# vrs6907.net
KiCad netlist of a schematic drawn in EAGLE
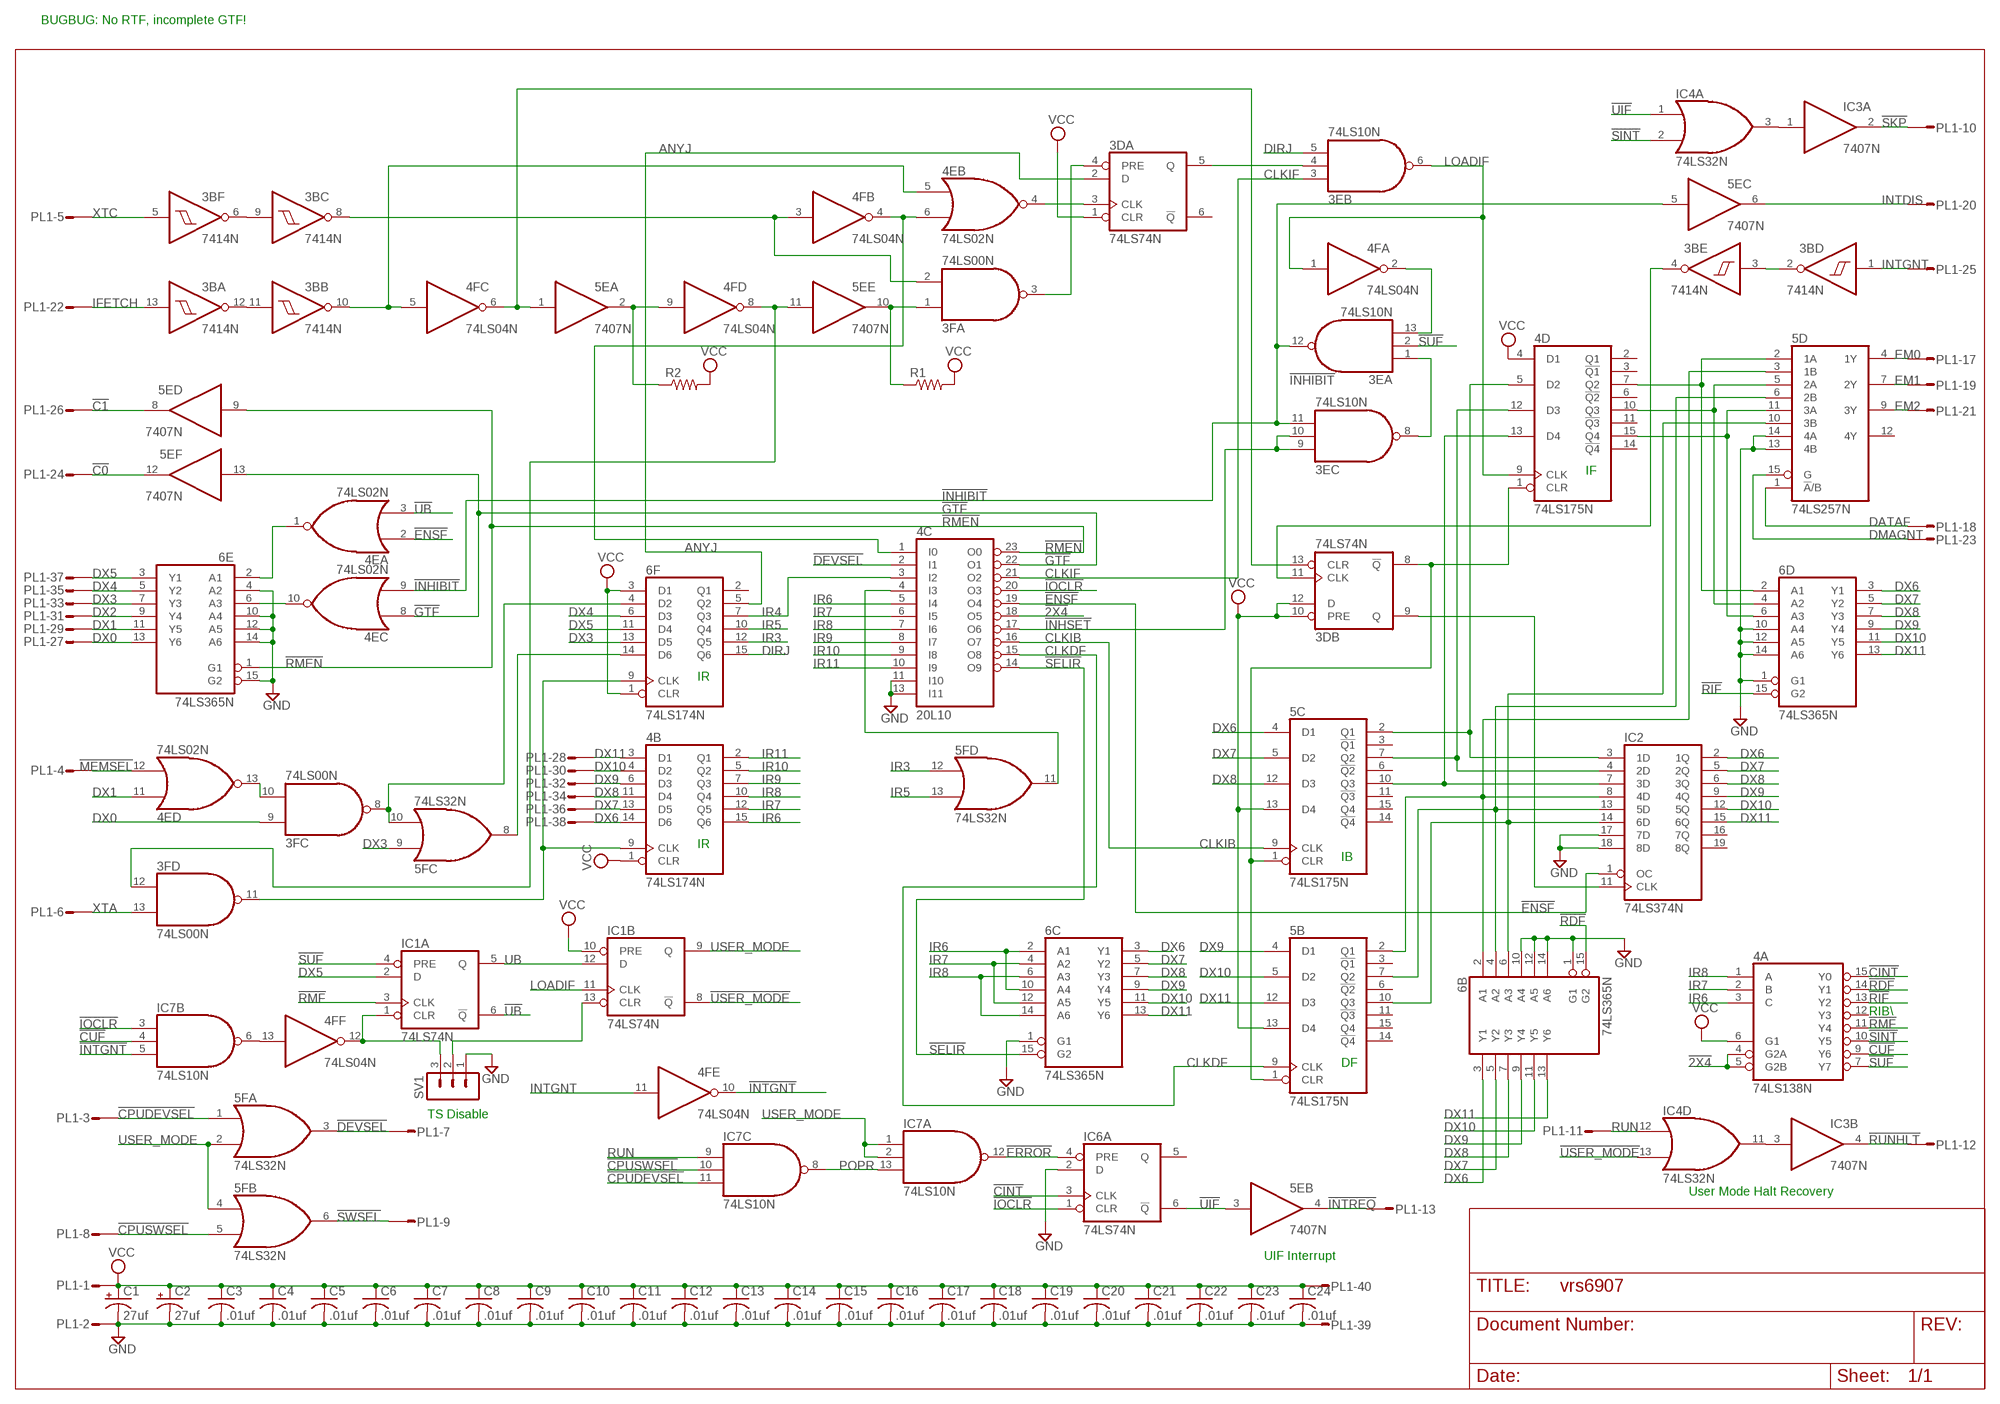
[diagram p0: schematic, sheet 1]

(export (version "E")
  (design (tool "Eeschema 10.0.6"))
  (components
    (comp (ref "3B")
      (value "7414N")
      (footprint "eagle-import:DIL14")
      (libsource (lib "eagle-import") (part "7414N"))
    )
    (comp (ref "3D")
      (value "74LS74N")
      (footprint "eagle-import:DIL14")
      (libsource (lib "eagle-import") (part "7474NLS"))
    )
    (comp (ref "3E")
      (value "74LS10N")
      (footprint "eagle-import:DIL14")
      (libsource (lib "eagle-import") (part "7410NLS"))
    )
    (comp (ref "3F")
      (value "74LS00N")
      (footprint "eagle-import:DIL14")
      (libsource (lib "eagle-import") (part "7400NLS"))
    )
    (comp (ref "4A")
      (value "74LS138N")
      (footprint "eagle-import:DIL16")
      (libsource (lib "eagle-import") (part "74138NLS"))
    )
    (comp (ref "4B")
      (value "74LS174N")
      (footprint "eagle-import:DIL16")
      (libsource (lib "eagle-import") (part "74174NLS"))
    )
    (comp (ref "4C")
      (value "20L10")
      (footprint "eagle-import:DIL24-3")
      (libsource (lib "eagle-import") (part "20L10"))
    )
    (comp (ref "4D")
      (value "74LS175N")
      (footprint "eagle-import:DIL16")
      (libsource (lib "eagle-import") (part "74175NLS"))
    )
    (comp (ref "4E")
      (value "74LS02N")
      (footprint "eagle-import:DIL14")
      (libsource (lib "eagle-import") (part "7402NLS"))
    )
    (comp (ref "4F")
      (value "74LS04N")
      (footprint "eagle-import:DIL14")
      (libsource (lib "eagle-import") (part "7404NLS"))
    )
    (comp (ref "5B")
      (value "74LS175N")
      (footprint "eagle-import:DIL16")
      (libsource (lib "eagle-import") (part "74175NLS"))
    )
    (comp (ref "5C")
      (value "74LS175N")
      (footprint "eagle-import:DIL16")
      (libsource (lib "eagle-import") (part "74175NLS"))
    )
    (comp (ref "5D")
      (value "74LS257N")
      (footprint "eagle-import:DIL16")
      (libsource (lib "eagle-import") (part "74257NLS"))
    )
    (comp (ref "5E")
      (value "7407N")
      (footprint "eagle-import:DIL14")
      (libsource (lib "eagle-import") (part "7407N"))
    )
    (comp (ref "5F")
      (value "74LS32N")
      (footprint "eagle-import:DIL14")
      (libsource (lib "eagle-import") (part "7432NLS"))
    )
    (comp (ref "6B")
      (value "74LS365N")
      (footprint "eagle-import:DIL16")
      (libsource (lib "eagle-import") (part "74365NLS"))
    )
    (comp (ref "6C")
      (value "74LS365N")
      (footprint "eagle-import:DIL16")
      (libsource (lib "eagle-import") (part "74365NLS"))
    )
    (comp (ref "6D")
      (value "74LS365N")
      (footprint "eagle-import:DIL16")
      (libsource (lib "eagle-import") (part "74365NLS"))
    )
    (comp (ref "6E")
      (value "74LS365N")
      (footprint "eagle-import:DIL16")
      (libsource (lib "eagle-import") (part "74365NLS"))
    )
    (comp (ref "6F")
      (value "74LS174N")
      (footprint "eagle-import:DIL16")
      (libsource (lib "eagle-import") (part "74174NLS"))
    )
    (comp (ref "C1")
      (value "27uf")
      (footprint "eagle-import:E22-6")
      (libsource (lib "eagle-import") (part "CPOL-USE22-6AXIAL"))
    )
    (comp (ref "C2")
      (value "27uf")
      (footprint "eagle-import:E22-6")
      (libsource (lib "eagle-import") (part "CPOL-USE22-6AXIAL"))
    )
    (comp (ref "C3")
      (value ".01uf")
      (footprint "eagle-import:C050-025X075")
      (libsource (lib "eagle-import") (part "C-US050-025X075"))
    )
    (comp (ref "C4")
      (value ".01uf")
      (footprint "eagle-import:C050-025X075")
      (libsource (lib "eagle-import") (part "C-US050-025X075"))
    )
    (comp (ref "C5")
      (value ".01uf")
      (footprint "eagle-import:C050-025X075")
      (libsource (lib "eagle-import") (part "C-US050-025X075"))
    )
    (comp (ref "C6")
      (value ".01uf")
      (footprint "eagle-import:C050-025X075")
      (libsource (lib "eagle-import") (part "C-US050-025X075"))
    )
    (comp (ref "C7")
      (value ".01uf")
      (footprint "eagle-import:C050-025X075")
      (libsource (lib "eagle-import") (part "C-US050-025X075"))
    )
    (comp (ref "C8")
      (value ".01uf")
      (footprint "eagle-import:C050-025X075")
      (libsource (lib "eagle-import") (part "C-US050-025X075"))
    )
    (comp (ref "C9")
      (value ".01uf")
      (footprint "eagle-import:C050-025X075")
      (libsource (lib "eagle-import") (part "C-US050-025X075"))
    )
    (comp (ref "C10")
      (value ".01uf")
      (footprint "eagle-import:C050-025X075")
      (libsource (lib "eagle-import") (part "C-US050-025X075"))
    )
    (comp (ref "C11")
      (value ".01uf")
      (footprint "eagle-import:C050-025X075")
      (libsource (lib "eagle-import") (part "C-US050-025X075"))
    )
    (comp (ref "C12")
      (value ".01uf")
      (footprint "eagle-import:C050-025X075")
      (libsource (lib "eagle-import") (part "C-US050-025X075"))
    )
    (comp (ref "C13")
      (value ".01uf")
      (footprint "eagle-import:C050-025X075")
      (libsource (lib "eagle-import") (part "C-US050-025X075"))
    )
    (comp (ref "C14")
      (value ".01uf")
      (footprint "eagle-import:C050-025X075")
      (libsource (lib "eagle-import") (part "C-US050-025X075"))
    )
    (comp (ref "C15")
      (value ".01uf")
      (footprint "eagle-import:C050-025X075")
      (libsource (lib "eagle-import") (part "C-US050-025X075"))
    )
    (comp (ref "C16")
      (value ".01uf")
      (footprint "eagle-import:C050-025X075")
      (libsource (lib "eagle-import") (part "C-US050-025X075"))
    )
    (comp (ref "C17")
      (value ".01uf")
      (footprint "eagle-import:C050-025X075")
      (libsource (lib "eagle-import") (part "C-US050-025X075"))
    )
    (comp (ref "C18")
      (value ".01uf")
      (footprint "eagle-import:C050-025X075")
      (libsource (lib "eagle-import") (part "C-US050-025X075"))
    )
    (comp (ref "C19")
      (value ".01uf")
      (footprint "eagle-import:C050-025X075")
      (libsource (lib "eagle-import") (part "C-US050-025X075"))
    )
    (comp (ref "C20")
      (value ".01uf")
      (footprint "eagle-import:C050-025X075")
      (libsource (lib "eagle-import") (part "C-US050-025X075"))
    )
    (comp (ref "C21")
      (value ".01uf")
      (footprint "eagle-import:C050-025X075")
      (libsource (lib "eagle-import") (part "C-US050-025X075"))
    )
    (comp (ref "C22")
      (value ".01uf")
      (footprint "eagle-import:C050-025X075")
      (libsource (lib "eagle-import") (part "C-US050-025X075"))
    )
    (comp (ref "C23")
      (value ".01uf")
      (footprint "eagle-import:C050-025X075")
      (libsource (lib "eagle-import") (part "C-US050-025X075"))
    )
    (comp (ref "C24")
      (value ".01uf")
      (footprint "eagle-import:C050-025X075")
      (libsource (lib "eagle-import") (part "C-US050-025X075"))
    )
    (comp (ref "IC1")
      (value "74LS74N")
      (footprint "eagle-import:DIL14")
      (libsource (lib "eagle-import") (part "7474NLS"))
    )
    (comp (ref "IC2")
      (value "74LS374N")
      (footprint "eagle-import:DIL20")
      (libsource (lib "eagle-import") (part "74374NLS"))
    )
    (comp (ref "IC3")
      (value "7407N")
      (footprint "eagle-import:DIL14")
      (libsource (lib "eagle-import") (part "7407N"))
    )
    (comp (ref "IC4")
      (value "74LS32N")
      (footprint "eagle-import:DIL14")
      (libsource (lib "eagle-import") (part "7432NLS"))
    )
    (comp (ref "IC6")
      (value "74LS74N")
      (footprint "eagle-import:DIL14")
      (libsource (lib "eagle-import") (part "7474NLS"))
    )
    (comp (ref "IC7")
      (value "74LS10N")
      (footprint "eagle-import:DIL14")
      (libsource (lib "eagle-import") (part "7410NLS"))
    )
    (comp (ref "PL1")
      (value "40VS")
      (footprint "eagle-import:40V")
      (libsource (lib "eagle-import") (part "40VS"))
    )
    (comp (ref "R1")
      (value "R-US_0207/10")
      (footprint "eagle-import:0207_10")
      (libsource (lib "eagle-import") (part "R-US_0207/10"))
    )
    (comp (ref "R2")
      (value "R-US_0207/10")
      (footprint "eagle-import:0207_10")
      (libsource (lib "eagle-import") (part "R-US_0207/10"))
    )
    (comp (ref "SV1")
      (value "MA03-1")
      (footprint "eagle-import:MA03-1")
      (libsource (lib "eagle-import") (part "MA03-1"))
    )
  )
  (nets
    (net (code "1") (name "/ANYJ") (class "Default")
      (node (ref "3D") (pin "2") (pinfunction "D_2") (pintype "input"))
      (node (ref "6F") (pin "5") (pinfunction "Q2_5") (pintype "output"))
    )
    (net (code "2") (name "/CLKDF") (class "Default")
      (node (ref "4C") (pin "15") (pinfunction "O8_15") (pintype "bidirectional"))
      (node (ref "5B") (pin "9") (pinfunction "CLK_9") (pintype "input"))
    )
    (net (code "3") (name "/CLKIB") (class "Default")
      (node (ref "4C") (pin "16") (pinfunction "O7_16") (pintype "bidirectional"))
      (node (ref "5C") (pin "9") (pinfunction "CLK_9") (pintype "input"))
    )
    (net (code "4") (name "/CLKIF") (class "Default")
      (node (ref "3E") (pin "3") (pinfunction "I0_3") (pintype "input"))
      (node (ref "4C") (pin "21") (pinfunction "O2_21") (pintype "bidirectional"))
    )
    (net (code "5") (name "/DATAF") (class "Default")
      (node (ref "5D") (pin "1") (pinfunction "~{A}/B_1") (pintype "input"))
      (node (ref "PL1") (pin "18") (pinfunction "S_18") (pintype "passive"))
    )
    (net (code "6") (name "/DIRJ") (class "Default")
      (node (ref "3E") (pin "5") (pinfunction "I2_5") (pintype "input"))
      (node (ref "6F") (pin "15") (pinfunction "Q6_15") (pintype "output"))
    )
    (net (code "7") (name "/DMAGNT") (class "Default")
      (node (ref "5D") (pin "15") (pinfunction "G_15") (pintype "input"))
      (node (ref "PL1") (pin "23") (pinfunction "S_23") (pintype "passive"))
    )
    (net (code "8") (name "/DX0") (class "Default")
      (node (ref "3F") (pin "9") (pinfunction "I0_9") (pintype "input"))
      (node (ref "6E") (pin "13") (pinfunction "Y6_13") (pintype "tri_state"))
      (node (ref "PL1") (pin "27") (pinfunction "S_27") (pintype "passive"))
    )
    (net (code "9") (name "/DX1") (class "Default")
      (node (ref "4E") (pin "11") (pinfunction "I0_11") (pintype "input"))
      (node (ref "6E") (pin "11") (pinfunction "Y5_11") (pintype "tri_state"))
      (node (ref "PL1") (pin "29") (pinfunction "S_29") (pintype "passive"))
    )
    (net (code "10") (name "/DX2") (class "Default")
      (node (ref "6E") (pin "9") (pinfunction "Y4_9") (pintype "tri_state"))
      (node (ref "PL1") (pin "31") (pinfunction "S_31") (pintype "passive"))
    )
    (net (code "11") (name "/DX3") (class "Default")
      (node (ref "5F") (pin "9") (pinfunction "I0_9") (pintype "input"))
      (node (ref "6E") (pin "7") (pinfunction "Y3_7") (pintype "tri_state"))
      (node (ref "6F") (pin "13") (pinfunction "D5_13") (pintype "input"))
      (node (ref "PL1") (pin "33") (pinfunction "S_33") (pintype "passive"))
    )
    (net (code "12") (name "/DX4") (class "Default")
      (node (ref "6E") (pin "5") (pinfunction "Y2_5") (pintype "tri_state"))
      (node (ref "6F") (pin "6") (pinfunction "D3_6") (pintype "input"))
      (node (ref "PL1") (pin "35") (pinfunction "S_35") (pintype "passive"))
    )
    (net (code "13") (name "/DX5") (class "Default")
      (node (ref "6E") (pin "3") (pinfunction "Y1_3") (pintype "tri_state"))
      (node (ref "6F") (pin "11") (pinfunction "D4_11") (pintype "input"))
      (node (ref "IC1") (pin "2") (pinfunction "D_2") (pintype "input"))
      (node (ref "PL1") (pin "37") (pinfunction "S_37") (pintype "passive"))
    )
    (net (code "14") (name "/DX6") (class "Default")
      (node (ref "4B") (pin "14") (pinfunction "D6_14") (pintype "input"))
      (node (ref "5C") (pin "4") (pinfunction "D1_4") (pintype "input"))
      (node (ref "6B") (pin "3") (pinfunction "Y1_3") (pintype "tri_state"))
      (node (ref "6C") (pin "3") (pinfunction "Y1_3") (pintype "tri_state"))
      (node (ref "6D") (pin "3") (pinfunction "Y1_3") (pintype "tri_state"))
      (node (ref "IC2") (pin "2") (pinfunction "1Q_2") (pintype "tri_state"))
      (node (ref "PL1") (pin "38") (pinfunction "S_38") (pintype "passive"))
    )
    (net (code "15") (name "/DX7") (class "Default")
      (node (ref "4B") (pin "13") (pinfunction "D5_13") (pintype "input"))
      (node (ref "5C") (pin "5") (pinfunction "D2_5") (pintype "input"))
      (node (ref "6B") (pin "5") (pinfunction "Y2_5") (pintype "tri_state"))
      (node (ref "6C") (pin "5") (pinfunction "Y2_5") (pintype "tri_state"))
      (node (ref "6D") (pin "5") (pinfunction "Y2_5") (pintype "tri_state"))
      (node (ref "IC2") (pin "5") (pinfunction "2Q_5") (pintype "tri_state"))
      (node (ref "PL1") (pin "36") (pinfunction "S_36") (pintype "passive"))
    )
    (net (code "16") (name "/DX8") (class "Default")
      (node (ref "4B") (pin "11") (pinfunction "D4_11") (pintype "input"))
      (node (ref "5C") (pin "12") (pinfunction "D3_12") (pintype "input"))
      (node (ref "6B") (pin "7") (pinfunction "Y3_7") (pintype "tri_state"))
      (node (ref "6C") (pin "7") (pinfunction "Y3_7") (pintype "tri_state"))
      (node (ref "6D") (pin "7") (pinfunction "Y3_7") (pintype "tri_state"))
      (node (ref "IC2") (pin "6") (pinfunction "3Q_6") (pintype "tri_state"))
      (node (ref "PL1") (pin "34") (pinfunction "S_34") (pintype "passive"))
    )
    (net (code "17") (name "/DX9") (class "Default")
      (node (ref "4B") (pin "6") (pinfunction "D3_6") (pintype "input"))
      (node (ref "5B") (pin "4") (pinfunction "D1_4") (pintype "input"))
      (node (ref "6B") (pin "9") (pinfunction "Y4_9") (pintype "tri_state"))
      (node (ref "6C") (pin "9") (pinfunction "Y4_9") (pintype "tri_state"))
      (node (ref "6D") (pin "9") (pinfunction "Y4_9") (pintype "tri_state"))
      (node (ref "IC2") (pin "9") (pinfunction "4Q_9") (pintype "tri_state"))
      (node (ref "PL1") (pin "32") (pinfunction "S_32") (pintype "passive"))
    )
    (net (code "18") (name "/DX10") (class "Default")
      (node (ref "4B") (pin "4") (pinfunction "D2_4") (pintype "input"))
      (node (ref "5B") (pin "5") (pinfunction "D2_5") (pintype "input"))
      (node (ref "6B") (pin "11") (pinfunction "Y5_11") (pintype "tri_state"))
      (node (ref "6C") (pin "11") (pinfunction "Y5_11") (pintype "tri_state"))
      (node (ref "6D") (pin "11") (pinfunction "Y5_11") (pintype "tri_state"))
      (node (ref "IC2") (pin "12") (pinfunction "5Q_12") (pintype "tri_state"))
      (node (ref "PL1") (pin "30") (pinfunction "S_30") (pintype "passive"))
    )
    (net (code "19") (name "/DX11") (class "Default")
      (node (ref "4B") (pin "3") (pinfunction "D1_3") (pintype "input"))
      (node (ref "5B") (pin "12") (pinfunction "D3_12") (pintype "input"))
      (node (ref "6B") (pin "13") (pinfunction "Y6_13") (pintype "tri_state"))
      (node (ref "6C") (pin "13") (pinfunction "Y6_13") (pintype "tri_state"))
      (node (ref "6D") (pin "13") (pinfunction "Y6_13") (pintype "tri_state"))
      (node (ref "IC2") (pin "15") (pinfunction "6Q_15") (pintype "tri_state"))
      (node (ref "PL1") (pin "28") (pinfunction "S_28") (pintype "passive"))
    )
    (net (code "20") (name "/EM0") (class "Default")
      (node (ref "5D") (pin "4") (pinfunction "1Y_4") (pintype "tri_state"))
      (node (ref "PL1") (pin "17") (pinfunction "S_17") (pintype "passive"))
    )
    (net (code "21") (name "/EM1") (class "Default")
      (node (ref "5D") (pin "7") (pinfunction "2Y_7") (pintype "tri_state"))
      (node (ref "PL1") (pin "19") (pinfunction "S_19") (pintype "passive"))
    )
    (net (code "22") (name "/EM2") (class "Default")
      (node (ref "5D") (pin "9") (pinfunction "3Y_9") (pintype "tri_state"))
      (node (ref "PL1") (pin "21") (pinfunction "S_21") (pintype "passive"))
    )
    (net (code "23") (name "/IFETCH") (class "Default")
      (node (ref "3B") (pin "13") (pinfunction "I_13") (pintype "input"))
      (node (ref "PL1") (pin "22") (pinfunction "S_22") (pintype "passive"))
    )
    (net (code "24") (name "/INTDIS") (class "Default")
      (node (ref "5E") (pin "6") (pinfunction "O_6") (pintype "open_collector"))
      (node (ref "PL1") (pin "20") (pinfunction "S_20") (pintype "passive"))
    )
    (net (code "25") (name "/INTGNT") (class "Default")
      (node (ref "3B") (pin "1") (pinfunction "I_1") (pintype "input"))
      (node (ref "4F") (pin "11") (pinfunction "I_11") (pintype "input"))
      (node (ref "PL1") (pin "25") (pinfunction "S_25") (pintype "passive"))
    )
    (net (code "26") (name "/IR3") (class "Default")
      (node (ref "5F") (pin "12") (pinfunction "I0_12") (pintype "input"))
      (node (ref "6F") (pin "12") (pinfunction "Q5_12") (pintype "output"))
    )
    (net (code "27") (name "/IR4") (class "Default")
      (node (ref "4C") (pin "3") (pinfunction "I2_3") (pintype "input"))
      (node (ref "6F") (pin "7") (pinfunction "Q3_7") (pintype "output"))
    )
    (net (code "28") (name "/IR5") (class "Default")
      (node (ref "5F") (pin "13") (pinfunction "I1_13") (pintype "input"))
      (node (ref "6F") (pin "10") (pinfunction "Q4_10") (pintype "output"))
    )
    (net (code "29") (name "/IR6") (class "Default")
      (node (ref "4A") (pin "3") (pinfunction "C_3") (pintype "input"))
      (node (ref "4B") (pin "15") (pinfunction "Q6_15") (pintype "output"))
      (node (ref "4C") (pin "5") (pinfunction "I4_5") (pintype "input"))
      (node (ref "6C") (pin "10") (pinfunction "A4_10") (pintype "input"))
      (node (ref "6C") (pin "2") (pinfunction "A1_2") (pintype "input"))
    )
    (net (code "30") (name "/IR7") (class "Default")
      (node (ref "4A") (pin "2") (pinfunction "B_2") (pintype "input"))
      (node (ref "4B") (pin "12") (pinfunction "Q5_12") (pintype "output"))
      (node (ref "4C") (pin "6") (pinfunction "I5_6") (pintype "input"))
      (node (ref "6C") (pin "12") (pinfunction "A5_12") (pintype "input"))
      (node (ref "6C") (pin "4") (pinfunction "A2_4") (pintype "input"))
    )
    (net (code "31") (name "/IR8") (class "Default")
      (node (ref "4A") (pin "1") (pinfunction "A_1") (pintype "input"))
      (node (ref "4B") (pin "10") (pinfunction "Q4_10") (pintype "output"))
      (node (ref "4C") (pin "7") (pinfunction "I6_7") (pintype "input"))
      (node (ref "6C") (pin "14") (pinfunction "A6_14") (pintype "input"))
      (node (ref "6C") (pin "6") (pinfunction "A3_6") (pintype "input"))
    )
    (net (code "32") (name "/IR9") (class "Default")
      (node (ref "4B") (pin "7") (pinfunction "Q3_7") (pintype "output"))
      (node (ref "4C") (pin "8") (pinfunction "I7_8") (pintype "input"))
    )
    (net (code "33") (name "/IR10") (class "Default")
      (node (ref "4B") (pin "5") (pinfunction "Q2_5") (pintype "output"))
      (node (ref "4C") (pin "9") (pinfunction "I8_9") (pintype "input"))
    )
    (net (code "34") (name "/IR11") (class "Default")
      (node (ref "4B") (pin "2") (pinfunction "Q1_2") (pintype "output"))
      (node (ref "4C") (pin "10") (pinfunction "I9_10") (pintype "input"))
    )
    (net (code "35") (name "/LOADIF") (class "Default")
      (node (ref "3E") (pin "6") (pinfunction "O_6") (pintype "output"))
      (node (ref "4D") (pin "9") (pinfunction "CLK_9") (pintype "input"))
      (node (ref "4F") (pin "1") (pinfunction "I_1") (pintype "input"))
      (node (ref "IC1") (pin "11") (pinfunction "CLK_11") (pintype "input"))
    )
    (net (code "36") (name "/POPR") (class "Default")
      (node (ref "IC7") (pin "13") (pinfunction "I2_13") (pintype "input"))
      (node (ref "IC7") (pin "8") (pinfunction "O_8") (pintype "output"))
    )
    (net (code "37") (name "/RUN") (class "Default")
      (node (ref "IC4") (pin "12") (pinfunction "I0_12") (pintype "input"))
      (node (ref "IC7") (pin "9") (pinfunction "I0_9") (pintype "input"))
      (node (ref "PL1") (pin "11") (pinfunction "S_11") (pintype "passive"))
    )
    (net (code "38") (name "/UB") (class "Default")
      (node (ref "IC1") (pin "12") (pinfunction "D_12") (pintype "input"))
      (node (ref "IC1") (pin "5") (pinfunction "Q_5") (pintype "output"))
    )
    (net (code "39") (name "/USER_MODE") (class "Default")
      (node (ref "5F") (pin "2") (pinfunction "I1_2") (pintype "input"))
      (node (ref "5F") (pin "4") (pinfunction "I0_4") (pintype "input"))
      (node (ref "IC1") (pin "9") (pinfunction "Q_9") (pintype "output"))
      (node (ref "IC7") (pin "1") (pinfunction "I0_1") (pintype "input"))
      (node (ref "IC7") (pin "2") (pinfunction "I1_2") (pintype "input"))
    )
    (net (code "40") (name "/XTA") (class "Default")
      (node (ref "3F") (pin "13") (pinfunction "I1_13") (pintype "input"))
      (node (ref "PL1") (pin "6") (pinfunction "S_6") (pintype "passive"))
    )
    (net (code "41") (name "/XTC") (class "Default")
      (node (ref "3B") (pin "5") (pinfunction "I_5") (pintype "input"))
      (node (ref "PL1") (pin "5") (pinfunction "S_5") (pintype "passive"))
    )
    (net (code "42") (name "/~{2X4}") (class "Default")
      (node (ref "4A") (pin "4") (pinfunction "G2A_4") (pintype "input"))
      (node (ref "4A") (pin "5") (pinfunction "G2B_5") (pintype "input"))
      (node (ref "4C") (pin "18") (pinfunction "O5_18") (pintype "bidirectional"))
    )
    (net (code "43") (name "/~{C0}") (class "Default")
      (node (ref "5E") (pin "12") (pinfunction "O_12") (pintype "open_collector"))
      (node (ref "PL1") (pin "24") (pinfunction "S_24") (pintype "passive"))
    )
    (net (code "44") (name "/~{C1}") (class "Default")
      (node (ref "5E") (pin "8") (pinfunction "O_8") (pintype "open_collector"))
      (node (ref "PL1") (pin "26") (pinfunction "S_26") (pintype "passive"))
    )
    (net (code "45") (name "/~{CINT}") (class "Default")
      (node (ref "4A") (pin "15") (pinfunction "Y0_15") (pintype "output"))
      (node (ref "IC6") (pin "3") (pinfunction "CLK_3") (pintype "input"))
    )
    (net (code "46") (name "/~{CPUDEVSEL}") (class "Default")
      (node (ref "5F") (pin "1") (pinfunction "I0_1") (pintype "input"))
      (node (ref "IC7") (pin "11") (pinfunction "I2_11") (pintype "input"))
      (node (ref "PL1") (pin "3") (pinfunction "S_3") (pintype "passive"))
    )
    (net (code "47") (name "/~{CPUSWSEL}") (class "Default")
      (node (ref "5F") (pin "5") (pinfunction "I1_5") (pintype "input"))
      (node (ref "IC7") (pin "10") (pinfunction "I1_10") (pintype "input"))
      (node (ref "PL1") (pin "8") (pinfunction "S_8") (pintype "passive"))
    )
    (net (code "48") (name "/~{CUF}") (class "Default")
      (node (ref "4A") (pin "9") (pinfunction "Y6_9") (pintype "output"))
      (node (ref "IC7") (pin "4") (pinfunction "I1_4") (pintype "input"))
    )
    (net (code "49") (name "/~{DEVSEL}") (class "Default")
      (node (ref "4C") (pin "2") (pinfunction "I1_2") (pintype "input"))
      (node (ref "5F") (pin "3") (pinfunction "O_3") (pintype "output"))
      (node (ref "PL1") (pin "7") (pinfunction "S_7") (pintype "passive"))
    )
    (net (code "50") (name "/~{ENSF}") (class "Default")
      (node (ref "4C") (pin "19") (pinfunction "O4_19") (pintype "bidirectional"))
      (node (ref "4E") (pin "2") (pinfunction "I0_2") (pintype "input"))
      (node (ref "IC2") (pin "1") (pinfunction "OC_1") (pintype "input"))
    )
    (net (code "51") (name "/~{ERROR}") (class "Default")
      (node (ref "IC6") (pin "4") (pinfunction "PRE_4") (pintype "input"))
      (node (ref "IC7") (pin "12") (pinfunction "O_12") (pintype "output"))
    )
    (net (code "52") (name "/~{GTF}") (class "Default")
      (node (ref "4C") (pin "22") (pinfunction "O1_22") (pintype "bidirectional"))
      (node (ref "4E") (pin "8") (pinfunction "I0_8") (pintype "input"))
      (node (ref "5E") (pin "13") (pinfunction "I_13") (pintype "input"))
    )
    (net (code "53") (name "/~{INHIBIT}") (class "Default")
      (node (ref "3E") (pin "11") (pinfunction "I2_11") (pintype "input"))
      (node (ref "3E") (pin "12") (pinfunction "O_12") (pintype "output"))
      (node (ref "4E") (pin "9") (pinfunction "I1_9") (pintype "input"))
      (node (ref "5E") (pin "5") (pinfunction "I_5") (pintype "input"))
    )
    (net (code "54") (name "/~{INHSET}") (class "Default")
      (node (ref "3E") (pin "10") (pinfunction "I1_10") (pintype "input"))
      (node (ref "3E") (pin "9") (pinfunction "I0_9") (pintype "input"))
      (node (ref "4C") (pin "17") (pinfunction "O6_17") (pintype "bidirectional"))
    )
    (net (code "55") (name "/~{INTGNT}") (class "Default")
      (node (ref "4F") (pin "10") (pinfunction "O_10") (pintype "output"))
      (node (ref "IC7") (pin "5") (pinfunction "I2_5") (pintype "input"))
    )
    (net (code "56") (name "/~{INTREQ}") (class "Default")
      (node (ref "5E") (pin "4") (pinfunction "O_4") (pintype "open_collector"))
      (node (ref "PL1") (pin "13") (pinfunction "S_13") (pintype "passive"))
    )
    (net (code "57") (name "/~{IOCLR}") (class "Default")
      (node (ref "4C") (pin "20") (pinfunction "O3_20") (pintype "bidirectional"))
      (node (ref "IC6") (pin "1") (pinfunction "CLR_1") (pintype "input"))
      (node (ref "IC7") (pin "3") (pinfunction "I0_3") (pintype "input"))
    )
    (net (code "58") (name "/~{MEMSEL}") (class "Default")
      (node (ref "4E") (pin "12") (pinfunction "I1_12") (pintype "input"))
      (node (ref "PL1") (pin "4") (pinfunction "S_4") (pintype "passive"))
    )
    (net (code "59") (name "/~{RDF}") (class "Default")
      (node (ref "4A") (pin "14") (pinfunction "Y1_14") (pintype "output"))
      (node (ref "6B") (pin "15") (pinfunction "G2_15") (pintype "input"))
    )
    (net (code "60") (name "/~{RIF}") (class "Default")
      (node (ref "4A") (pin "13") (pinfunction "Y2_13") (pintype "output"))
      (node (ref "6D") (pin "15") (pinfunction "G2_15") (pintype "input"))
    )
    (net (code "61") (name "/~{RMEN}") (class "Default")
      (node (ref "4C") (pin "23") (pinfunction "O0_23") (pintype "output"))
      (node (ref "5E") (pin "9") (pinfunction "I_9") (pintype "input"))
      (node (ref "6E") (pin "1") (pinfunction "G1_1") (pintype "input"))
    )
    (net (code "62") (name "/~{RMF}") (class "Default")
      (node (ref "4A") (pin "11") (pinfunction "Y4_11") (pintype "output"))
      (node (ref "IC1") (pin "3") (pinfunction "CLK_3") (pintype "input"))
    )
    (net (code "63") (name "/~{RUNHLT}") (class "Default")
      (node (ref "IC3") (pin "4") (pinfunction "O_4") (pintype "open_collector"))
      (node (ref "PL1") (pin "12") (pinfunction "S_12") (pintype "passive"))
    )
    (net (code "64") (name "/~{SELIR}") (class "Default")
      (node (ref "4C") (pin "14") (pinfunction "O9_14") (pintype "output"))
      (node (ref "6C") (pin "15") (pinfunction "G2_15") (pintype "input"))
    )
    (net (code "65") (name "/~{SINT}") (class "Default")
      (node (ref "4A") (pin "10") (pinfunction "Y5_10") (pintype "output"))
      (node (ref "IC4") (pin "2") (pinfunction "I1_2") (pintype "input"))
    )
    (net (code "66") (name "/~{SKP}") (class "Default")
      (node (ref "IC3") (pin "2") (pinfunction "O_2") (pintype "open_collector"))
      (node (ref "PL1") (pin "10") (pinfunction "S_10") (pintype "passive"))
    )
    (net (code "67") (name "/~{SUF}") (class "Default")
      (node (ref "3E") (pin "2") (pinfunction "I1_2") (pintype "input"))
      (node (ref "4A") (pin "7") (pinfunction "Y7_7") (pintype "output"))
      (node (ref "IC1") (pin "4") (pinfunction "PRE_4") (pintype "input"))
    )
    (net (code "68") (name "/~{SWSEL}") (class "Default")
      (node (ref "5F") (pin "6") (pinfunction "O_6") (pintype "output"))
      (node (ref "PL1") (pin "9") (pinfunction "S_9") (pintype "passive"))
    )
    (net (code "69") (name "/~{UB}") (class "Default")
      (node (ref "4E") (pin "3") (pinfunction "I1_3") (pintype "input"))
      (node (ref "IC1") (pin "6") (pinfunction "~{Q}_6") (pintype "output"))
    )
    (net (code "70") (name "/~{UIF}") (class "Default")
      (node (ref "5E") (pin "3") (pinfunction "I_3") (pintype "input"))
      (node (ref "IC4") (pin "1") (pinfunction "I0_1") (pintype "input"))
      (node (ref "IC6") (pin "6") (pinfunction "~{Q}_6") (pintype "output"))
    )
    (net (code "71") (name "/~{USER_MODE}") (class "Default")
      (node (ref "IC1") (pin "8") (pinfunction "~{Q}_8") (pintype "output"))
      (node (ref "IC4") (pin "13") (pinfunction "I1_13") (pintype "input"))
    )
    (net (code "72") (name "GND") (class "Default")
      (node (ref "4C") (pin "11") (pinfunction "I10_11") (pintype "input"))
      (node (ref "4C") (pin "13") (pinfunction "I11_13") (pintype "input"))
      (node (ref "5D") (pin "13") (pinfunction "4B_13") (pintype "input"))
      (node (ref "5D") (pin "14") (pinfunction "4A_14") (pintype "input"))
      (node (ref "6B") (pin "1") (pinfunction "G1_1") (pintype "input"))
      (node (ref "6B") (pin "10") (pinfunction "A4_10") (pintype "input"))
      (node (ref "6B") (pin "12") (pinfunction "A5_12") (pintype "input"))
      (node (ref "6B") (pin "14") (pinfunction "A6_14") (pintype "input"))
      (node (ref "6C") (pin "1") (pinfunction "G1_1") (pintype "input"))
      (node (ref "6D") (pin "1") (pinfunction "G1_1") (pintype "input"))
      (node (ref "6D") (pin "10") (pinfunction "A4_10") (pintype "input"))
      (node (ref "6D") (pin "12") (pinfunction "A5_12") (pintype "input"))
      (node (ref "6D") (pin "14") (pinfunction "A6_14") (pintype "input"))
      (node (ref "6E") (pin "10") (pinfunction "A4_10") (pintype "input"))
      (node (ref "6E") (pin "12") (pinfunction "A5_12") (pintype "input"))
      (node (ref "6E") (pin "14") (pinfunction "A6_14") (pintype "input"))
      (node (ref "6E") (pin "15") (pinfunction "G2_15") (pintype "input"))
      (node (ref "6E") (pin "4") (pinfunction "A2_4") (pintype "input"))
      (node (ref "C1") (pin "-") (pinfunction "-_-") (pintype "passive"))
      (node (ref "C10") (pin "2") (pinfunction "2_2") (pintype "passive"))
      (node (ref "C11") (pin "2") (pinfunction "2_2") (pintype "passive"))
      (node (ref "C12") (pin "2") (pinfunction "2_2") (pintype "passive"))
      (node (ref "C13") (pin "2") (pinfunction "2_2") (pintype "passive"))
      (node (ref "C14") (pin "2") (pinfunction "2_2") (pintype "passive"))
      (node (ref "C15") (pin "2") (pinfunction "2_2") (pintype "passive"))
      (node (ref "C16") (pin "2") (pinfunction "2_2") (pintype "passive"))
      (node (ref "C17") (pin "2") (pinfunction "2_2") (pintype "passive"))
      (node (ref "C18") (pin "2") (pinfunction "2_2") (pintype "passive"))
      (node (ref "C19") (pin "2") (pinfunction "2_2") (pintype "passive"))
      (node (ref "C2") (pin "-") (pinfunction "-_-") (pintype "passive"))
      (node (ref "C20") (pin "2") (pinfunction "2_2") (pintype "passive"))
      (node (ref "C21") (pin "2") (pinfunction "2_2") (pintype "passive"))
      (node (ref "C22") (pin "2") (pinfunction "2_2") (pintype "passive"))
      (node (ref "C23") (pin "2") (pinfunction "2_2") (pintype "passive"))
      (node (ref "C24") (pin "2") (pinfunction "2_2") (pintype "passive"))
      (node (ref "C3") (pin "2") (pinfunction "2_2") (pintype "passive"))
      (node (ref "C4") (pin "2") (pinfunction "2_2") (pintype "passive"))
      (node (ref "C5") (pin "2") (pinfunction "2_2") (pintype "passive"))
      (node (ref "C6") (pin "2") (pinfunction "2_2") (pintype "passive"))
      (node (ref "C7") (pin "2") (pinfunction "2_2") (pintype "passive"))
      (node (ref "C8") (pin "2") (pinfunction "2_2") (pintype "passive"))
      (node (ref "C9") (pin "2") (pinfunction "2_2") (pintype "passive"))
      (node (ref "IC2") (pin "17") (pinfunction "7D_17") (pintype "input"))
      (node (ref "IC2") (pin "18") (pinfunction "8D_18") (pintype "input"))
      (node (ref "IC6") (pin "2") (pinfunction "D_2") (pintype "input"))
      (node (ref "PL1") (pin "2") (pinfunction "S_2") (pintype "passive"))
      (node (ref "PL1") (pin "39") (pinfunction "S_39") (pintype "passive"))
      (node (ref "SV1") (pin "1") (pinfunction "1_1") (pintype "passive"))
    )
    (net (code "73") (name "Net-(3BA-O)") (class "Default")
      (node (ref "3B") (pin "11") (pinfunction "I_11") (pintype "input"))
      (node (ref "3B") (pin "12") (pinfunction "O_12") (pintype "output"))
    )
    (net (code "74") (name "Net-(3BB-O)") (class "Default")
      (node (ref "3B") (pin "10") (pinfunction "O_10") (pintype "output"))
      (node (ref "4E") (pin "5") (pinfunction "I0_5") (pintype "input"))
      (node (ref "4F") (pin "5") (pinfunction "I_5") (pintype "input"))
    )
    (net (code "75") (name "Net-(3BC-I)") (class "Default")
      (node (ref "3B") (pin "6") (pinfunction "O_6") (pintype "output"))
      (node (ref "3B") (pin "9") (pinfunction "I_9") (pintype "input"))
    )
    (net (code "76") (name "Net-(3BC-O)") (class "Default")
      (node (ref "3B") (pin "8") (pinfunction "O_8") (pintype "output"))
      (node (ref "3F") (pin "2") (pinfunction "I1_2") (pintype "input"))
      (node (ref "4F") (pin "3") (pinfunction "I_3") (pintype "input"))
    )
    (net (code "77") (name "Net-(3BD-O)") (class "Default")
      (node (ref "3B") (pin "2") (pinfunction "O_2") (pintype "output"))
      (node (ref "3B") (pin "3") (pinfunction "I_3") (pintype "input"))
    )
    (net (code "78") (name "Net-(3BE-O)") (class "Default")
      (node (ref "3B") (pin "4") (pinfunction "O_4") (pintype "output"))
      (node (ref "3D") (pin "11") (pinfunction "CLK_11") (pintype "input"))
    )
    (net (code "79") (name "Net-(3DA-CLK)") (class "Default")
      (node (ref "3D") (pin "3") (pinfunction "CLK_3") (pintype "input"))
      (node (ref "4E") (pin "4") (pinfunction "O_4") (pintype "output"))
    )
    (net (code "80") (name "Net-(3DA-PRE)") (class "Default")
      (node (ref "3D") (pin "4") (pinfunction "PRE_4") (pintype "input"))
      (node (ref "3F") (pin "3") (pinfunction "O_3") (pintype "output"))
    )
    (net (code "81") (name "Net-(3DA-Q)") (class "Default")
      (node (ref "3D") (pin "5") (pinfunction "Q_5") (pintype "output"))
      (node (ref "3E") (pin "4") (pinfunction "I1_4") (pintype "input"))
    )
    (net (code "82") (name "Net-(3DB-CLR)") (class "Default")
      (node (ref "3D") (pin "13") (pinfunction "CLR_13") (pintype "input"))
      (node (ref "4F") (pin "6") (pinfunction "O_6") (pintype "output"))
      (node (ref "5E") (pin "1") (pinfunction "I_1") (pintype "input"))
    )
    (net (code "83") (name "Net-(3DB-Q)") (class "Default")
      (node (ref "3D") (pin "9") (pinfunction "Q_9") (pintype "output"))
      (node (ref "IC2") (pin "11") (pinfunction "CLK_11") (pintype "input"))
    )
    (net (code "84") (name "Net-(3DB-~{Q})") (class "Default")
      (node (ref "3D") (pin "8") (pinfunction "~{Q}_8") (pintype "output"))
      (node (ref "4D") (pin "1") (pinfunction "CLR_1") (pintype "input"))
      (node (ref "5B") (pin "1") (pinfunction "CLR_1") (pintype "input"))
      (node (ref "5C") (pin "1") (pinfunction "CLR_1") (pintype "input"))
    )
    (net (code "85") (name "Net-(3EA-I0)") (class "Default")
      (node (ref "3E") (pin "1") (pinfunction "I0_1") (pintype "input"))
      (node (ref "3E") (pin "8") (pinfunction "O_8") (pintype "output"))
    )
    (net (code "86") (name "Net-(3EA-I2)") (class "Default")
      (node (ref "3E") (pin "13") (pinfunction "I2_13") (pintype "input"))
      (node (ref "4F") (pin "2") (pinfunction "O_2") (pintype "output"))
    )
    (net (code "87") (name "Net-(3FA-I0)") (class "Default")
      (node (ref "3F") (pin "1") (pinfunction "I0_1") (pintype "input"))
      (node (ref "5E") (pin "10") (pinfunction "O_10") (pintype "open_collector"))
      (node (ref "R1") (pin "1") (pinfunction "1_1") (pintype "passive"))
    )
    (net (code "88") (name "Net-(3FC-I1)") (class "Default")
      (node (ref "3F") (pin "10") (pinfunction "I1_10") (pintype "input"))
      (node (ref "4E") (pin "13") (pinfunction "O_13") (pintype "output"))
    )
    (net (code "89") (name "Net-(3FC-O)") (class "Default")
      (node (ref "3F") (pin "8") (pinfunction "O_8") (pintype "output"))
      (node (ref "5F") (pin "10") (pinfunction "I1_10") (pintype "input"))
      (node (ref "6F") (pin "4") (pinfunction "D2_4") (pintype "input"))
    )
    (net (code "90") (name "Net-(3FD-I0)") (class "Default")
      (node (ref "3F") (pin "12") (pinfunction "I0_12") (pintype "input"))
      (node (ref "4F") (pin "8") (pinfunction "O_8") (pintype "output"))
      (node (ref "5E") (pin "11") (pinfunction "I_11") (pintype "input"))
    )
    (net (code "91") (name "Net-(3FD-O)") (class "Default")
      (node (ref "3F") (pin "11") (pinfunction "O_11") (pintype "output"))
      (node (ref "4B") (pin "9") (pinfunction "CLK_9") (pintype "input"))
      (node (ref "6F") (pin "9") (pinfunction "CLK_9") (pintype "input"))
    )
    (net (code "92") (name "Net-(4CA-I0)") (class "Default")
      (node (ref "4C") (pin "1") (pinfunction "I0_1") (pintype "input"))
      (node (ref "4E") (pin "6") (pinfunction "I1_6") (pintype "input"))
      (node (ref "4F") (pin "4") (pinfunction "O_4") (pintype "output"))
    )
    (net (code "93") (name "Net-(4CA-I3)") (class "Default")
      (node (ref "4C") (pin "4") (pinfunction "I3_4") (pintype "input"))
      (node (ref "5F") (pin "11") (pinfunction "O_11") (pintype "output"))
    )
    (net (code "94") (name "Net-(4DA-D2)") (class "Default")
      (node (ref "4D") (pin "5") (pinfunction "D2_5") (pintype "input"))
      (node (ref "5C") (pin "2") (pinfunction "Q1_2") (pintype "output"))
      (node (ref "IC2") (pin "3") (pinfunction "1D_3") (pintype "input"))
    )
    (net (code "95") (name "Net-(4DA-D3)") (class "Default")
      (node (ref "4D") (pin "12") (pinfunction "D3_12") (pintype "input"))
      (node (ref "5C") (pin "7") (pinfunction "Q2_7") (pintype "output"))
      (node (ref "IC2") (pin "4") (pinfunction "2D_4") (pintype "input"))
    )
    (net (code "96") (name "Net-(4DA-D4)") (class "Default")
      (node (ref "4D") (pin "13") (pinfunction "D4_13") (pintype "input"))
      (node (ref "5C") (pin "10") (pinfunction "Q3_10") (pintype "output"))
      (node (ref "IC2") (pin "7") (pinfunction "3D_7") (pintype "input"))
    )
    (net (code "97") (name "Net-(4DA-Q2)") (class "Default")
      (node (ref "4D") (pin "7") (pinfunction "Q2_7") (pintype "output"))
      (node (ref "5D") (pin "2") (pinfunction "1A_2") (pintype "input"))
      (node (ref "6D") (pin "2") (pinfunction "A1_2") (pintype "input"))
    )
    (net (code "98") (name "Net-(4DA-Q3)") (class "Default")
      (node (ref "4D") (pin "10") (pinfunction "Q3_10") (pintype "output"))
      (node (ref "5D") (pin "5") (pinfunction "2A_5") (pintype "input"))
      (node (ref "6D") (pin "4") (pinfunction "A2_4") (pintype "input"))
    )
    (net (code "99") (name "Net-(4DA-Q4)") (class "Default")
      (node (ref "4D") (pin "15") (pinfunction "Q4_15") (pintype "output"))
      (node (ref "5D") (pin "11") (pinfunction "3A_11") (pintype "input"))
      (node (ref "6D") (pin "6") (pinfunction "A3_6") (pintype "input"))
    )
    (net (code "100") (name "Net-(4EA-O)") (class "Default")
      (node (ref "4E") (pin "1") (pinfunction "O_1") (pintype "output"))
      (node (ref "6E") (pin "2") (pinfunction "A1_2") (pintype "input"))
    )
    (net (code "101") (name "Net-(4EC-O)") (class "Default")
      (node (ref "4E") (pin "10") (pinfunction "O_10") (pintype "output"))
      (node (ref "6E") (pin "6") (pinfunction "A3_6") (pintype "input"))
    )
    (net (code "102") (name "Net-(4FD-I)") (class "Default")
      (node (ref "4F") (pin "9") (pinfunction "I_9") (pintype "input"))
      (node (ref "5E") (pin "2") (pinfunction "O_2") (pintype "open_collector"))
      (node (ref "R2") (pin "1") (pinfunction "1_1") (pintype "passive"))
    )
    (net (code "103") (name "Net-(4FF-I)") (class "Default")
      (node (ref "4F") (pin "13") (pinfunction "I_13") (pintype "input"))
      (node (ref "IC7") (pin "6") (pinfunction "O_6") (pintype "output"))
    )
    (net (code "104") (name "Net-(4FF-O)") (class "Default")
      (node (ref "4F") (pin "12") (pinfunction "O_12") (pintype "output"))
      (node (ref "IC1") (pin "1") (pinfunction "CLR_1") (pintype "input"))
      (node (ref "SV1") (pin "3") (pinfunction "3_3") (pintype "passive"))
    )
    (net (code "105") (name "Net-(5BA-Q1)") (class "Default")
      (node (ref "5B") (pin "2") (pinfunction "Q1_2") (pintype "output"))
      (node (ref "5D") (pin "3") (pinfunction "1B_3") (pintype "input"))
      (node (ref "6B") (pin "2") (pinfunction "A1_2") (pintype "input"))
      (node (ref "IC2") (pin "8") (pinfunction "4D_8") (pintype "input"))
    )
    (net (code "106") (name "Net-(5BA-Q2)") (class "Default")
      (node (ref "5B") (pin "7") (pinfunction "Q2_7") (pintype "output"))
      (node (ref "5D") (pin "6") (pinfunction "2B_6") (pintype "input"))
      (node (ref "6B") (pin "4") (pinfunction "A2_4") (pintype "input"))
      (node (ref "IC2") (pin "13") (pinfunction "5D_13") (pintype "input"))
    )
    (net (code "107") (name "Net-(5BA-Q3)") (class "Default")
      (node (ref "5B") (pin "10") (pinfunction "Q3_10") (pintype "output"))
      (node (ref "5D") (pin "10") (pinfunction "3B_10") (pintype "input"))
      (node (ref "6B") (pin "6") (pinfunction "A3_6") (pintype "input"))
      (node (ref "IC2") (pin "14") (pinfunction "6D_14") (pintype "input"))
    )
    (net (code "108") (name "Net-(5FC-O)") (class "Default")
      (node (ref "5F") (pin "8") (pinfunction "O_8") (pintype "output"))
      (node (ref "6F") (pin "14") (pinfunction "D6_14") (pintype "input"))
    )
    (net (code "109") (name "Net-(IC1B-CLR)") (class "Default")
      (node (ref "IC1") (pin "13") (pinfunction "CLR_13") (pintype "input"))
      (node (ref "SV1") (pin "2") (pinfunction "2_2") (pintype "passive"))
    )
    (net (code "110") (name "Net-(IC3A-I)") (class "Default")
      (node (ref "IC3") (pin "1") (pinfunction "I_1") (pintype "input"))
      (node (ref "IC4") (pin "3") (pinfunction "O_3") (pintype "output"))
    )
    (net (code "111") (name "Net-(IC3B-I)") (class "Default")
      (node (ref "IC3") (pin "3") (pinfunction "I_3") (pintype "input"))
      (node (ref "IC4") (pin "11") (pinfunction "O_11") (pintype "output"))
    )
    (net (code "112") (name "VCC") (class "Default")
      (node (ref "3D") (pin "1") (pinfunction "CLR_1") (pintype "input"))
      (node (ref "3D") (pin "10") (pinfunction "PRE_10") (pintype "input"))
      (node (ref "3D") (pin "12") (pinfunction "D_12") (pintype "input"))
      (node (ref "4A") (pin "6") (pinfunction "G1_6") (pintype "input"))
      (node (ref "4B") (pin "1") (pinfunction "CLR_1") (pintype "input"))
      (node (ref "4D") (pin "4") (pinfunction "D1_4") (pintype "input"))
      (node (ref "5B") (pin "13") (pinfunction "D4_13") (pintype "input"))
      (node (ref "5C") (pin "13") (pinfunction "D4_13") (pintype "input"))
      (node (ref "6F") (pin "1") (pinfunction "CLR_1") (pintype "input"))
      (node (ref "6F") (pin "3") (pinfunction "D1_3") (pintype "input"))
      (node (ref "C1") (pin "+") (pinfunction "+_+") (pintype "passive"))
      (node (ref "C10") (pin "1") (pinfunction "1_1") (pintype "passive"))
      (node (ref "C11") (pin "1") (pinfunction "1_1") (pintype "passive"))
      (node (ref "C12") (pin "1") (pinfunction "1_1") (pintype "passive"))
      (node (ref "C13") (pin "1") (pinfunction "1_1") (pintype "passive"))
      (node (ref "C14") (pin "1") (pinfunction "1_1") (pintype "passive"))
      (node (ref "C15") (pin "1") (pinfunction "1_1") (pintype "passive"))
      (node (ref "C16") (pin "1") (pinfunction "1_1") (pintype "passive"))
      (node (ref "C17") (pin "1") (pinfunction "1_1") (pintype "passive"))
      (node (ref "C18") (pin "1") (pinfunction "1_1") (pintype "passive"))
      (node (ref "C19") (pin "1") (pinfunction "1_1") (pintype "passive"))
      (node (ref "C2") (pin "+") (pinfunction "+_+") (pintype "passive"))
      (node (ref "C20") (pin "1") (pinfunction "1_1") (pintype "passive"))
      (node (ref "C21") (pin "1") (pinfunction "1_1") (pintype "passive"))
      (node (ref "C22") (pin "1") (pinfunction "1_1") (pintype "passive"))
      (node (ref "C23") (pin "1") (pinfunction "1_1") (pintype "passive"))
      (node (ref "C24") (pin "1") (pinfunction "1_1") (pintype "passive"))
      (node (ref "C3") (pin "1") (pinfunction "1_1") (pintype "passive"))
      (node (ref "C4") (pin "1") (pinfunction "1_1") (pintype "passive"))
      (node (ref "C5") (pin "1") (pinfunction "1_1") (pintype "passive"))
      (node (ref "C6") (pin "1") (pinfunction "1_1") (pintype "passive"))
      (node (ref "C7") (pin "1") (pinfunction "1_1") (pintype "passive"))
      (node (ref "C8") (pin "1") (pinfunction "1_1") (pintype "passive"))
      (node (ref "C9") (pin "1") (pinfunction "1_1") (pintype "passive"))
      (node (ref "IC1") (pin "10") (pinfunction "PRE_10") (pintype "input"))
      (node (ref "PL1") (pin "1") (pinfunction "S_1") (pintype "passive"))
      (node (ref "PL1") (pin "40") (pinfunction "S_40") (pintype "passive"))
      (node (ref "R1") (pin "2") (pinfunction "2_2") (pintype "passive"))
      (node (ref "R2") (pin "2") (pinfunction "2_2") (pintype "passive"))
    )
    (net (code "113") (name "unconnected-(3DA-~{Q}-Pad6)") (class "Default")
      (node (ref "3D") (pin "6") (pinfunction "~{Q}_6") (pintype "output"))
    )
    (net (code "114") (name "unconnected-(4AA-Y3-Pad12)") (class "Default")
      (node (ref "4A") (pin "12") (pinfunction "Y3_12") (pintype "output"))
    )
    (net (code "115") (name "unconnected-(4DA-Q1-Pad2)") (class "Default")
      (node (ref "4D") (pin "2") (pinfunction "Q1_2") (pintype "output"))
    )
    (net (code "116") (name "unconnected-(4DA-~{Q1}-Pad3)") (class "Default")
      (node (ref "4D") (pin "3") (pinfunction "~{Q1}_3") (pintype "output"))
    )
    (net (code "117") (name "unconnected-(4DA-~{Q2}-Pad6)") (class "Default")
      (node (ref "4D") (pin "6") (pinfunction "~{Q2}_6") (pintype "output"))
    )
    (net (code "118") (name "unconnected-(4DA-~{Q3}-Pad11)") (class "Default")
      (node (ref "4D") (pin "11") (pinfunction "~{Q3}_11") (pintype "output"))
    )
    (net (code "119") (name "unconnected-(4DA-~{Q4}-Pad14)") (class "Default")
      (node (ref "4D") (pin "14") (pinfunction "~{Q4}_14") (pintype "output"))
    )
    (net (code "120") (name "unconnected-(5BA-Q4-Pad15)") (class "Default")
      (node (ref "5B") (pin "15") (pinfunction "Q4_15") (pintype "output"))
    )
    (net (code "121") (name "unconnected-(5BA-~{Q1}-Pad3)") (class "Default")
      (node (ref "5B") (pin "3") (pinfunction "~{Q1}_3") (pintype "output"))
    )
    (net (code "122") (name "unconnected-(5BA-~{Q2}-Pad6)") (class "Default")
      (node (ref "5B") (pin "6") (pinfunction "~{Q2}_6") (pintype "output"))
    )
    (net (code "123") (name "unconnected-(5BA-~{Q3}-Pad11)") (class "Default")
      (node (ref "5B") (pin "11") (pinfunction "~{Q3}_11") (pintype "output"))
    )
    (net (code "124") (name "unconnected-(5BA-~{Q4}-Pad14)") (class "Default")
      (node (ref "5B") (pin "14") (pinfunction "~{Q4}_14") (pintype "output"))
    )
    (net (code "125") (name "unconnected-(5CA-Q4-Pad15)") (class "Default")
      (node (ref "5C") (pin "15") (pinfunction "Q4_15") (pintype "output"))
    )
    (net (code "126") (name "unconnected-(5CA-~{Q1}-Pad3)") (class "Default")
      (node (ref "5C") (pin "3") (pinfunction "~{Q1}_3") (pintype "output"))
    )
    (net (code "127") (name "unconnected-(5CA-~{Q2}-Pad6)") (class "Default")
      (node (ref "5C") (pin "6") (pinfunction "~{Q2}_6") (pintype "output"))
    )
    (net (code "128") (name "unconnected-(5CA-~{Q3}-Pad11)") (class "Default")
      (node (ref "5C") (pin "11") (pinfunction "~{Q3}_11") (pintype "output"))
    )
    (net (code "129") (name "unconnected-(5CA-~{Q4}-Pad14)") (class "Default")
      (node (ref "5C") (pin "14") (pinfunction "~{Q4}_14") (pintype "output"))
    )
    (net (code "130") (name "unconnected-(5DA-4Y-Pad12)") (class "Default")
      (node (ref "5D") (pin "12") (pinfunction "4Y_12") (pintype "tri_state"))
    )
    (net (code "131") (name "unconnected-(6FA-Q1-Pad2)") (class "Default")
      (node (ref "6F") (pin "2") (pinfunction "Q1_2") (pintype "output"))
    )
    (net (code "132") (name "unconnected-(IC2A-7Q-Pad16)") (class "Default")
      (node (ref "IC2") (pin "16") (pinfunction "7Q_16") (pintype "tri_state"))
    )
    (net (code "133") (name "unconnected-(IC2A-8Q-Pad19)") (class "Default")
      (node (ref "IC2") (pin "19") (pinfunction "8Q_19") (pintype "tri_state"))
    )
    (net (code "134") (name "unconnected-(IC6A-Q-Pad5)") (class "Default")
      (node (ref "IC6") (pin "5") (pinfunction "Q_5") (pintype "output"))
    )
  )
)
